# Twintig-USB.net
KiCad netlist of a schematic drawn in Altium Designer
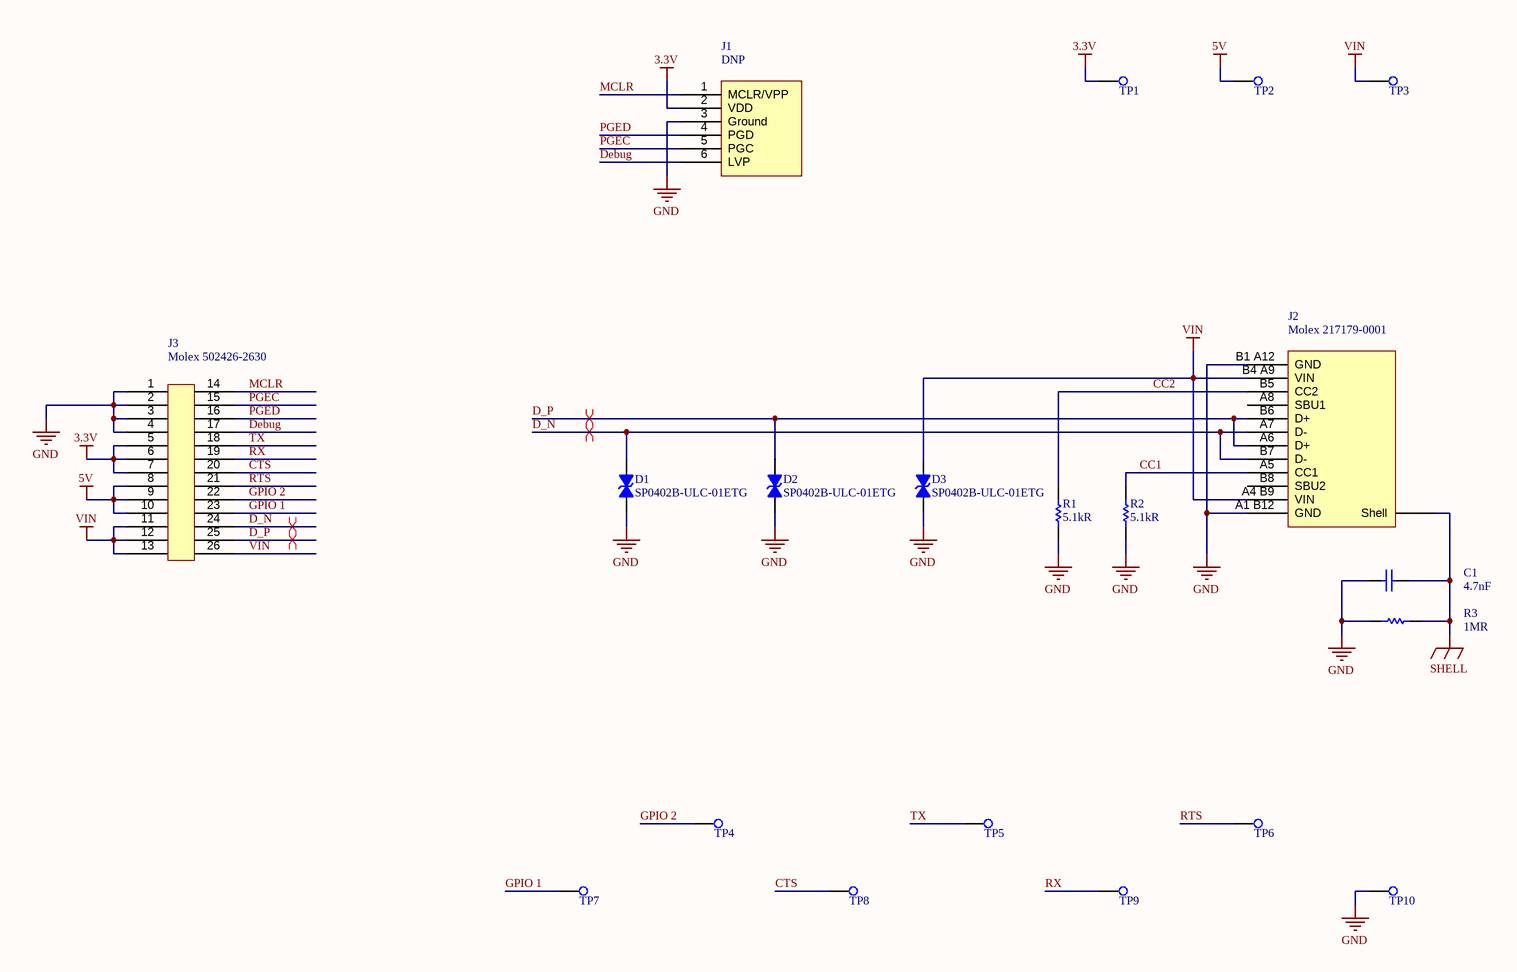
[diagram p0: Twintig-USB.SchDoc]

(export (version "E")
  (design (tool "Eeschema 10.0.6"))
  (components
    (comp (ref "C1") (value "4.7nF") (footprint "Capacitor 0402") (libsource (lib "x-io") (part "Capacitor")))
    (comp (ref "D1")
      (value "SP0402B-ULC-01ETG")
      (footprint "Diode TVS 0402")
      (libsource (lib "x-io") (part "Diode TVS"))
    )
    (comp (ref "D2")
      (value "SP0402B-ULC-01ETG")
      (footprint "Diode TVS 0402")
      (libsource (lib "x-io") (part "Diode TVS"))
    )
    (comp (ref "D3")
      (value "SP0402B-ULC-01ETG")
      (footprint "Diode TVS 0402")
      (libsource (lib "x-io") (part "Diode TVS"))
    )
    (comp (ref "J1")
      (value "DNP")
      (footprint "Tag Connect No Legs")
      (libsource (lib "x-io") (part "MPLAB ICSP"))
    )
    (comp (ref "J2")
      (value "Molex 217179-0001")
      (footprint "Molex 217179-0001")
      (libsource (lib "x-io") (part "USB-C Receptacle (16 Pin)"))
    )
    (comp (ref "J3")
      (value "Molex 502426-2630")
      (footprint "Molex 502426-2630")
      (libsource (lib "x-io") (part "Molex 502426-2630"))
    )
    (comp (ref "R1") (value "5.1kR") (footprint "Resistor 0402") (libsource (lib "x-io") (part "Resistor")))
    (comp (ref "R2") (value "5.1kR") (footprint "Resistor 0402") (libsource (lib "x-io") (part "Resistor")))
    (comp (ref "R3") (value "1MR") (footprint "Resistor 0402") (libsource (lib "x-io") (part "Resistor")))
    (comp (ref "TP1")
      (value "Test Point")
      (footprint "Test Point 1.5mm")
      (libsource (lib "x-io") (part "Test Point"))
    )
    (comp (ref "TP2")
      (value "Test Point")
      (footprint "Test Point 1.5mm")
      (libsource (lib "x-io") (part "Test Point"))
    )
    (comp (ref "TP3")
      (value "Test Point")
      (footprint "Test Point 1.5mm")
      (libsource (lib "x-io") (part "Test Point"))
    )
    (comp (ref "TP4")
      (value "Test Point")
      (footprint "Test Point 1.5mm")
      (libsource (lib "x-io") (part "Test Point"))
    )
    (comp (ref "TP5")
      (value "Test Point")
      (footprint "Test Point 1.5mm")
      (libsource (lib "x-io") (part "Test Point"))
    )
    (comp (ref "TP6")
      (value "Test Point")
      (footprint "Test Point 1.5mm")
      (libsource (lib "x-io") (part "Test Point"))
    )
    (comp (ref "TP7")
      (value "Test Point")
      (footprint "Test Point 1.5mm")
      (libsource (lib "x-io") (part "Test Point"))
    )
    (comp (ref "TP8")
      (value "Test Point")
      (footprint "Test Point 1.5mm")
      (libsource (lib "x-io") (part "Test Point"))
    )
    (comp (ref "TP9")
      (value "Test Point")
      (footprint "Test Point 1.5mm")
      (libsource (lib "x-io") (part "Test Point"))
    )
    (comp (ref "TP10")
      (value "Test Point")
      (footprint "Test Point 1.5mm")
      (libsource (lib "x-io") (part "Test Point"))
    )
  )
  (nets
    (net (code "1") (name "/CC1") (class "Default")
      (node (ref "J2") (pin "A5") (pinfunction "CC1_A5") (pintype "passive"))
      (node (ref "R2") (pin "2") (pinfunction "2_2") (pintype "passive"))
    )
    (net (code "2") (name "/CC2") (class "Default")
      (node (ref "J2") (pin "B5") (pinfunction "CC2_B5") (pintype "passive"))
      (node (ref "R1") (pin "2") (pinfunction "2_2") (pintype "passive"))
    )
    (net (code "3") (name "/CTS") (class "Default")
      (node (ref "J3") (pin "20") (pinfunction "20_20") (pintype "passive"))
      (node (ref "TP8") (pin "1") (pinfunction "1_1") (pintype "passive"))
    )
    (net (code "4") (name "/D_N") (class "Default")
      (node (ref "D1") (pin "1") (pinfunction "*_1") (pintype "passive"))
      (node (ref "J2") (pin "A7") (pinfunction "D-_A7") (pintype "passive"))
      (node (ref "J2") (pin "B7") (pinfunction "D-_B7") (pintype "passive"))
      (node (ref "J3") (pin "24") (pinfunction "24_24") (pintype "passive"))
    )
    (net (code "5") (name "/D_P") (class "Default")
      (node (ref "D2") (pin "1") (pinfunction "*_1") (pintype "passive"))
      (node (ref "J2") (pin "A6") (pinfunction "D+_A6") (pintype "passive"))
      (node (ref "J2") (pin "B6") (pinfunction "D+_B6") (pintype "passive"))
      (node (ref "J3") (pin "25") (pinfunction "25_25") (pintype "passive"))
    )
    (net (code "6") (name "/Debug") (class "Default")
      (node (ref "J1") (pin "6") (pinfunction "LVP_6") (pintype "passive"))
      (node (ref "J3") (pin "17") (pinfunction "17_17") (pintype "passive"))
    )
    (net (code "7") (name "/GPIO 1") (class "Default")
      (node (ref "J3") (pin "23") (pinfunction "23_23") (pintype "passive"))
      (node (ref "TP7") (pin "1") (pinfunction "1_1") (pintype "passive"))
    )
    (net (code "8") (name "/GPIO 2") (class "Default")
      (node (ref "J3") (pin "22") (pinfunction "22_22") (pintype "passive"))
      (node (ref "TP4") (pin "1") (pinfunction "1_1") (pintype "passive"))
    )
    (net (code "9") (name "/MCLR") (class "Default")
      (node (ref "J1") (pin "1") (pinfunction "MCLR/VPP_1") (pintype "passive"))
      (node (ref "J3") (pin "14") (pinfunction "14_14") (pintype "passive"))
    )
    (net (code "10") (name "/PGEC") (class "Default")
      (node (ref "J1") (pin "5") (pinfunction "PGC_5") (pintype "passive"))
      (node (ref "J3") (pin "15") (pinfunction "15_15") (pintype "passive"))
    )
    (net (code "11") (name "/PGED") (class "Default")
      (node (ref "J1") (pin "4") (pinfunction "PGD_4") (pintype "passive"))
      (node (ref "J3") (pin "16") (pinfunction "16_16") (pintype "passive"))
    )
    (net (code "12") (name "/RTS") (class "Default")
      (node (ref "J3") (pin "21") (pinfunction "21_21") (pintype "passive"))
      (node (ref "TP6") (pin "1") (pinfunction "1_1") (pintype "passive"))
    )
    (net (code "13") (name "/RX") (class "Default")
      (node (ref "J3") (pin "19") (pinfunction "19_19") (pintype "passive"))
      (node (ref "TP9") (pin "1") (pinfunction "1_1") (pintype "passive"))
    )
    (net (code "14") (name "/TX") (class "Default")
      (node (ref "J3") (pin "18") (pinfunction "18_18") (pintype "passive"))
      (node (ref "TP5") (pin "1") (pinfunction "1_1") (pintype "passive"))
    )
    (net (code "15") (name "3.3V") (class "Default")
      (node (ref "J1") (pin "2") (pinfunction "VDD_2") (pintype "passive"))
      (node (ref "J3") (pin "5") (pinfunction "5_5") (pintype "passive"))
      (node (ref "J3") (pin "6") (pinfunction "6_6") (pintype "passive"))
      (node (ref "J3") (pin "7") (pinfunction "7_7") (pintype "passive"))
      (node (ref "TP1") (pin "1") (pinfunction "1_1") (pintype "passive"))
    )
    (net (code "16") (name "5V") (class "Default")
      (node (ref "J3") (pin "10") (pinfunction "10_10") (pintype "passive"))
      (node (ref "J3") (pin "8") (pinfunction "8_8") (pintype "passive"))
      (node (ref "J3") (pin "9") (pinfunction "9_9") (pintype "passive"))
      (node (ref "TP2") (pin "1") (pinfunction "1_1") (pintype "passive"))
    )
    (net (code "17") (name "GND") (class "Default")
      (node (ref "C1") (pin "2") (pinfunction "2_2") (pintype "passive"))
      (node (ref "D1") (pin "2") (pinfunction "*_2") (pintype "passive"))
      (node (ref "D2") (pin "2") (pinfunction "*_2") (pintype "passive"))
      (node (ref "D3") (pin "2") (pinfunction "*_2") (pintype "passive"))
      (node (ref "J1") (pin "3") (pinfunction "Ground_3") (pintype "passive"))
      (node (ref "J2") (pin "A1_B12") (pinfunction "GND_A1_B12") (pintype "passive"))
      (node (ref "J2") (pin "B1_A12") (pinfunction "GND_B1_A12") (pintype "passive"))
      (node (ref "J3") (pin "1") (pinfunction "1_1") (pintype "passive"))
      (node (ref "J3") (pin "2") (pinfunction "2_2") (pintype "passive"))
      (node (ref "J3") (pin "3") (pinfunction "3_3") (pintype "passive"))
      (node (ref "J3") (pin "4") (pinfunction "4_4") (pintype "passive"))
      (node (ref "R1") (pin "1") (pinfunction "1_1") (pintype "passive"))
      (node (ref "R2") (pin "1") (pinfunction "1_1") (pintype "passive"))
      (node (ref "R3") (pin "2") (pinfunction "2_2") (pintype "passive"))
      (node (ref "TP10") (pin "1") (pinfunction "1_1") (pintype "passive"))
    )
    (net (code "18") (name "SHELL") (class "Default")
      (node (ref "C1") (pin "1") (pinfunction "1_1") (pintype "passive"))
      (node (ref "J2") (pin "Shell") (pinfunction "Shell_Shell") (pintype "passive"))
      (node (ref "R3") (pin "1") (pinfunction "1_1") (pintype "passive"))
    )
    (net (code "19") (name "VIN") (class "Default")
      (node (ref "D3") (pin "1") (pinfunction "*_1") (pintype "passive"))
      (node (ref "J2") (pin "A4_B9") (pinfunction "VIN_A4_B9") (pintype "passive"))
      (node (ref "J2") (pin "B4_A9") (pinfunction "VIN_B4_A9") (pintype "passive"))
      (node (ref "J3") (pin "11") (pinfunction "11_11") (pintype "passive"))
      (node (ref "J3") (pin "12") (pinfunction "12_12") (pintype "passive"))
      (node (ref "J3") (pin "13") (pinfunction "13_13") (pintype "passive"))
      (node (ref "J3") (pin "26") (pinfunction "26_26") (pintype "passive"))
      (node (ref "TP3") (pin "1") (pinfunction "1_1") (pintype "passive"))
    )
    (net (code "20") (name "unconnected-(J2-SBU1-PadA8)") (class "Default")
      (node (ref "J2") (pin "A8") (pinfunction "SBU1_A8") (pintype "passive"))
    )
    (net (code "21") (name "unconnected-(J2-SBU2-PadB8)") (class "Default")
      (node (ref "J2") (pin "B8") (pinfunction "SBU2_B8") (pintype "passive"))
    )
  )
)
